# S-Puck-mcu.net
KiCad netlist of a schematic drawn in EAGLE
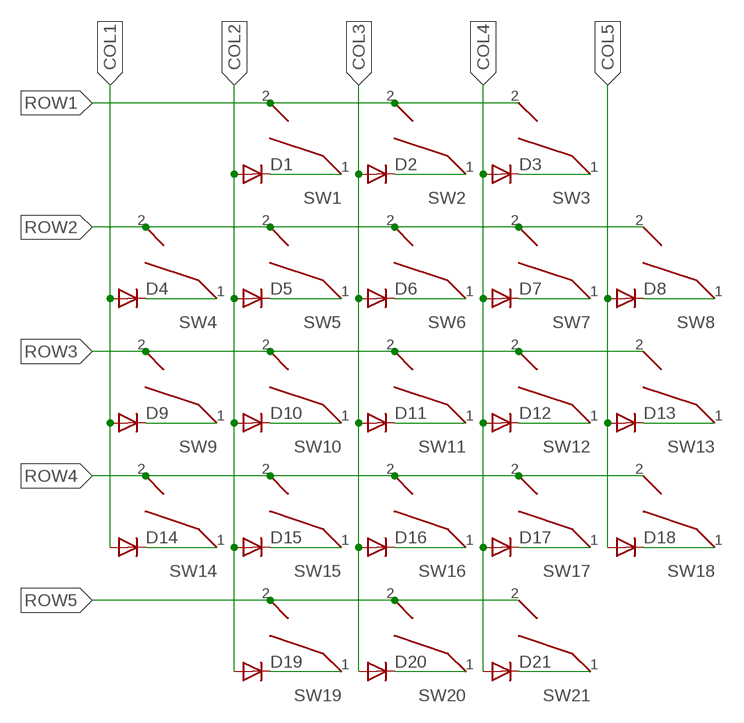
[diagram p0: schematic, sheet 1]
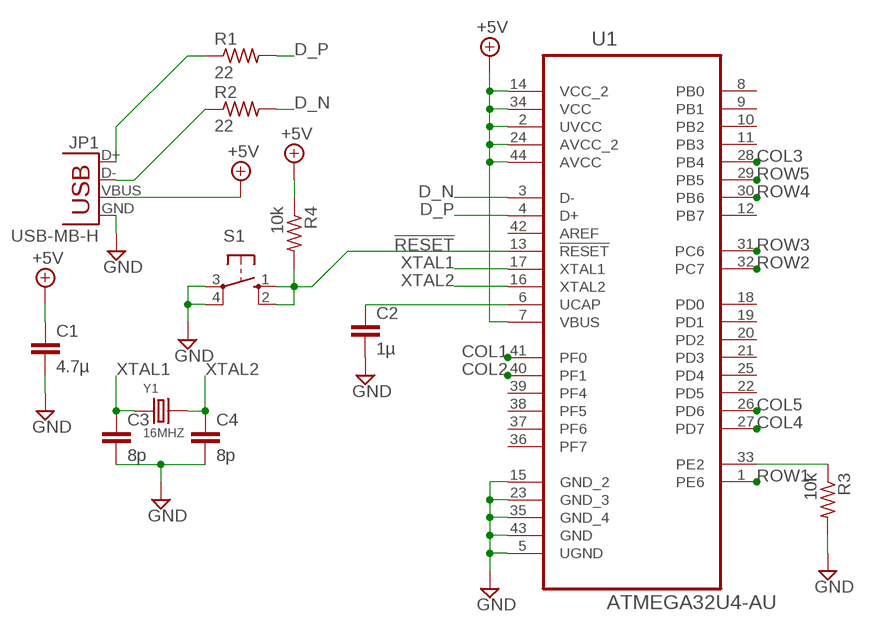
[diagram p1: schematic, sheet 2]

(export (version "E")
  (design (tool "Eeschema 10.0.6"))
  (components
    (comp (ref "D1")
      (value "1N4148DO35-10")
      (footprint "eagle-import:DO35-10")
      (libsource (lib "eagle-import") (part "1N4148DO35-10"))
    )
    (comp (ref "D2")
      (value "1N4148DO35-10")
      (footprint "eagle-import:DO35-10")
      (libsource (lib "eagle-import") (part "1N4148DO35-10"))
    )
    (comp (ref "D3")
      (value "1N4148DO35-10")
      (footprint "eagle-import:DO35-10")
      (libsource (lib "eagle-import") (part "1N4148DO35-10"))
    )
    (comp (ref "D4")
      (value "1N4148DO35-10")
      (footprint "eagle-import:DO35-10")
      (libsource (lib "eagle-import") (part "1N4148DO35-10"))
    )
    (comp (ref "D5")
      (value "1N4148DO35-10")
      (footprint "eagle-import:DO35-10")
      (libsource (lib "eagle-import") (part "1N4148DO35-10"))
    )
    (comp (ref "D6")
      (value "1N4148DO35-10")
      (footprint "eagle-import:DO35-10")
      (libsource (lib "eagle-import") (part "1N4148DO35-10"))
    )
    (comp (ref "D7")
      (value "1N4148DO35-10")
      (footprint "eagle-import:DO35-10")
      (libsource (lib "eagle-import") (part "1N4148DO35-10"))
    )
    (comp (ref "D8")
      (value "1N4148DO35-10")
      (footprint "eagle-import:DO35-10")
      (libsource (lib "eagle-import") (part "1N4148DO35-10"))
    )
    (comp (ref "D9")
      (value "1N4148DO35-10")
      (footprint "eagle-import:DO35-10")
      (libsource (lib "eagle-import") (part "1N4148DO35-10"))
    )
    (comp (ref "D10")
      (value "1N4148DO35-10")
      (footprint "eagle-import:DO35-10")
      (libsource (lib "eagle-import") (part "1N4148DO35-10"))
    )
    (comp (ref "D11")
      (value "1N4148DO35-10")
      (footprint "eagle-import:DO35-10")
      (libsource (lib "eagle-import") (part "1N4148DO35-10"))
    )
    (comp (ref "D12")
      (value "1N4148DO35-10")
      (footprint "eagle-import:DO35-10")
      (libsource (lib "eagle-import") (part "1N4148DO35-10"))
    )
    (comp (ref "D13")
      (value "1N4148DO35-10")
      (footprint "eagle-import:DO35-10")
      (libsource (lib "eagle-import") (part "1N4148DO35-10"))
    )
    (comp (ref "D14")
      (value "1N4148DO35-10")
      (footprint "eagle-import:DO35-10")
      (libsource (lib "eagle-import") (part "1N4148DO35-10"))
    )
    (comp (ref "D15")
      (value "1N4148DO35-10")
      (footprint "eagle-import:DO35-10")
      (libsource (lib "eagle-import") (part "1N4148DO35-10"))
    )
    (comp (ref "D16")
      (value "1N4148DO35-10")
      (footprint "eagle-import:DO35-10")
      (libsource (lib "eagle-import") (part "1N4148DO35-10"))
    )
    (comp (ref "D17")
      (value "1N4148DO35-10")
      (footprint "eagle-import:DO35-10")
      (libsource (lib "eagle-import") (part "1N4148DO35-10"))
    )
    (comp (ref "D18")
      (value "1N4148DO35-10")
      (footprint "eagle-import:DO35-10")
      (libsource (lib "eagle-import") (part "1N4148DO35-10"))
    )
    (comp (ref "D19")
      (value "1N4148DO35-10")
      (footprint "eagle-import:DO35-10")
      (libsource (lib "eagle-import") (part "1N4148DO35-10"))
    )
    (comp (ref "D20")
      (value "1N4148DO35-10")
      (footprint "eagle-import:DO35-10")
      (libsource (lib "eagle-import") (part "1N4148DO35-10"))
    )
    (comp (ref "D21")
      (value "1N4148DO35-10")
      (footprint "eagle-import:DO35-10")
      (libsource (lib "eagle-import") (part "1N4148DO35-10"))
    )
    (comp (ref "SW1")
      (value "CHERRY_MX_WITH_FIXING_PINS")
      (footprint "eagle-import:MX1A-XXNW")
      (libsource (lib "eagle-import") (part "CHERRY_MX_WITH_FIXING_PINS"))
    )
    (comp (ref "SW2")
      (value "CHERRY_MX_WITH_FIXING_PINS")
      (footprint "eagle-import:MX1A-XXNW")
      (libsource (lib "eagle-import") (part "CHERRY_MX_WITH_FIXING_PINS"))
    )
    (comp (ref "SW3")
      (value "CHERRY_MX_WITH_FIXING_PINS")
      (footprint "eagle-import:MX1A-XXNW")
      (libsource (lib "eagle-import") (part "CHERRY_MX_WITH_FIXING_PINS"))
    )
    (comp (ref "SW4")
      (value "CHERRY_MX_WITH_FIXING_PINS")
      (footprint "eagle-import:MX1A-XXNW")
      (libsource (lib "eagle-import") (part "CHERRY_MX_WITH_FIXING_PINS"))
    )
    (comp (ref "SW5")
      (value "CHERRY_MX_WITH_FIXING_PINS")
      (footprint "eagle-import:MX1A-XXNW")
      (libsource (lib "eagle-import") (part "CHERRY_MX_WITH_FIXING_PINS"))
    )
    (comp (ref "SW6")
      (value "CHERRY_MX_WITH_FIXING_PINS")
      (footprint "eagle-import:MX1A-XXNW")
      (libsource (lib "eagle-import") (part "CHERRY_MX_WITH_FIXING_PINS"))
    )
    (comp (ref "SW7")
      (value "CHERRY_MX_WITH_FIXING_PINS")
      (footprint "eagle-import:MX1A-XXNW")
      (libsource (lib "eagle-import") (part "CHERRY_MX_WITH_FIXING_PINS"))
    )
    (comp (ref "SW8")
      (value "CHERRY_MX_WITH_FIXING_PINS")
      (footprint "eagle-import:MX1A-XXNW")
      (libsource (lib "eagle-import") (part "CHERRY_MX_WITH_FIXING_PINS"))
    )
    (comp (ref "SW9")
      (value "CHERRY_MX_WITH_FIXING_PINS")
      (footprint "eagle-import:MX1A-XXNW")
      (libsource (lib "eagle-import") (part "CHERRY_MX_WITH_FIXING_PINS"))
    )
    (comp (ref "SW10")
      (value "CHERRY_MX_WITH_FIXING_PINS")
      (footprint "eagle-import:MX1A-XXNW")
      (libsource (lib "eagle-import") (part "CHERRY_MX_WITH_FIXING_PINS"))
    )
    (comp (ref "SW11")
      (value "CHERRY_MX_WITH_FIXING_PINS")
      (footprint "eagle-import:MX1A-XXNW")
      (libsource (lib "eagle-import") (part "CHERRY_MX_WITH_FIXING_PINS"))
    )
    (comp (ref "SW12")
      (value "CHERRY_MX_WITH_FIXING_PINS")
      (footprint "eagle-import:MX1A-XXNW")
      (libsource (lib "eagle-import") (part "CHERRY_MX_WITH_FIXING_PINS"))
    )
    (comp (ref "SW13")
      (value "CHERRY_MX_WITH_FIXING_PINS")
      (footprint "eagle-import:MX1A-XXNW")
      (libsource (lib "eagle-import") (part "CHERRY_MX_WITH_FIXING_PINS"))
    )
    (comp (ref "SW14")
      (value "CHERRY_MX_WITH_FIXING_PINS")
      (footprint "eagle-import:MX1A-XXNW")
      (libsource (lib "eagle-import") (part "CHERRY_MX_WITH_FIXING_PINS"))
    )
    (comp (ref "SW15")
      (value "CHERRY_MX_WITH_FIXING_PINS")
      (footprint "eagle-import:MX1A-XXNW")
      (libsource (lib "eagle-import") (part "CHERRY_MX_WITH_FIXING_PINS"))
    )
    (comp (ref "SW16")
      (value "CHERRY_MX_WITH_FIXING_PINS")
      (footprint "eagle-import:MX1A-XXNW")
      (libsource (lib "eagle-import") (part "CHERRY_MX_WITH_FIXING_PINS"))
    )
    (comp (ref "SW17")
      (value "CHERRY_MX_WITH_FIXING_PINS")
      (footprint "eagle-import:MX1A-XXNW")
      (libsource (lib "eagle-import") (part "CHERRY_MX_WITH_FIXING_PINS"))
    )
    (comp (ref "SW18")
      (value "CHERRY_MX_WITH_FIXING_PINS")
      (footprint "eagle-import:MX1A-XXNW")
      (libsource (lib "eagle-import") (part "CHERRY_MX_WITH_FIXING_PINS"))
    )
    (comp (ref "SW19")
      (value "CHERRY_MX_WITH_FIXING_PINS")
      (footprint "eagle-import:MX1A-XXNW")
      (libsource (lib "eagle-import") (part "CHERRY_MX_WITH_FIXING_PINS"))
    )
    (comp (ref "SW20")
      (value "CHERRY_MX_WITH_FIXING_PINS")
      (footprint "eagle-import:MX1A-XXNW")
      (libsource (lib "eagle-import") (part "CHERRY_MX_WITH_FIXING_PINS"))
    )
    (comp (ref "SW21")
      (value "CHERRY_MX_WITH_FIXING_PINS")
      (footprint "eagle-import:MX1A-XXNW")
      (libsource (lib "eagle-import") (part "CHERRY_MX_WITH_FIXING_PINS"))
    )
    (comp (ref "C1")
      (value "4.7µ")
      (footprint "eagle-import:C0805K")
      (libsource (lib "eagle-import") (part "C-EUC0805K"))
    )
    (comp (ref "C2")
      (value "1µ")
      (footprint "eagle-import:C0805K")
      (libsource (lib "eagle-import") (part "C-EUC0805K"))
    )
    (comp (ref "C3")
      (value "8p")
      (footprint "eagle-import:C0805K")
      (libsource (lib "eagle-import") (part "C-EUC0805K"))
    )
    (comp (ref "C4")
      (value "8p")
      (footprint "eagle-import:C0805K")
      (libsource (lib "eagle-import") (part "C-EUC0805K"))
    )
    (comp (ref "JP1")
      (value "USB-MB-H")
      (footprint "eagle-import:USB-MB-H")
      (libsource (lib "eagle-import") (part "USB-MB-H"))
    )
    (comp (ref "R1")
      (value "22")
      (footprint "eagle-import:R0805W")
      (libsource (lib "eagle-import") (part "R-US_R0805W"))
    )
    (comp (ref "R2")
      (value "22")
      (footprint "eagle-import:R0805W")
      (libsource (lib "eagle-import") (part "R-US_R0805W"))
    )
    (comp (ref "R3")
      (value "10k")
      (footprint "eagle-import:R0805W")
      (libsource (lib "eagle-import") (part "R-US_R0805W"))
    )
    (comp (ref "R4")
      (value "10k")
      (footprint "eagle-import:R0805W")
      (libsource (lib "eagle-import") (part "R-US_R0805W"))
    )
    (comp (ref "S1")
      (value "10-XX")
      (footprint "eagle-import:B3F-10XX")
      (fields (field (name "MPN") "B3F-1000"))
      (libsource (lib "eagle-import") (part "10-XX"))
    )
    (comp (ref "U1")
      (value "ATMEGA32U4-AU")
      (footprint "eagle-import:QFP80P1200X1200X120-44N")
      (libsource (lib "eagle-import") (part "ATMEGA32U4-AU"))
    )
    (comp (ref "Y1")
      (value "16MHZ")
      (footprint "eagle-import:X2-SMD-5.0X3.2X1.3MM")
      (fields (field (name "MPN") "X053201602002"))
      (libsource (lib "eagle-import") (part "SMD-CRYSTAL-16MHZ-8PF-20PPM-40R(2P-5.0X3.2MM)"))
    )
  )
  (nets
    (net (code "1") (name "+5V") (class "Default")
      (node (ref "C1") (pin "1") (pinfunction "1_1") (pintype "passive"))
      (node (ref "JP1") (pin "VBUS") (pinfunction "VBUS_VBUS") (pintype "bidirectional"))
      (node (ref "R4") (pin "1") (pinfunction "1_1") (pintype "passive"))
      (node (ref "U1") (pin "14") (pinfunction "VCC_2_14") (pintype "power_in"))
      (node (ref "U1") (pin "2") (pinfunction "UVCC_2") (pintype "power_in"))
      (node (ref "U1") (pin "24") (pinfunction "AVCC_2_24") (pintype "power_in"))
      (node (ref "U1") (pin "34") (pinfunction "VCC_34") (pintype "power_in"))
      (node (ref "U1") (pin "44") (pinfunction "AVCC_44") (pintype "power_in"))
      (node (ref "U1") (pin "7") (pinfunction "VBUS_7") (pintype "input"))
    )
    (net (code "2") (name "COL1") (class "Default")
      (node (ref "D14") (pin "A") (pinfunction "A_A") (pintype "passive"))
      (node (ref "D4") (pin "A") (pinfunction "A_A") (pintype "passive"))
      (node (ref "D9") (pin "A") (pinfunction "A_A") (pintype "passive"))
      (node (ref "U1") (pin "41") (pinfunction "PF0_41") (pintype "bidirectional"))
    )
    (net (code "3") (name "COL2") (class "Default")
      (node (ref "D1") (pin "A") (pinfunction "A_A") (pintype "passive"))
      (node (ref "D10") (pin "A") (pinfunction "A_A") (pintype "passive"))
      (node (ref "D15") (pin "A") (pinfunction "A_A") (pintype "passive"))
      (node (ref "D19") (pin "A") (pinfunction "A_A") (pintype "passive"))
      (node (ref "D5") (pin "A") (pinfunction "A_A") (pintype "passive"))
      (node (ref "U1") (pin "40") (pinfunction "PF1_40") (pintype "bidirectional"))
    )
    (net (code "4") (name "COL3") (class "Default")
      (node (ref "D11") (pin "A") (pinfunction "A_A") (pintype "passive"))
      (node (ref "D16") (pin "A") (pinfunction "A_A") (pintype "passive"))
      (node (ref "D2") (pin "A") (pinfunction "A_A") (pintype "passive"))
      (node (ref "D20") (pin "A") (pinfunction "A_A") (pintype "passive"))
      (node (ref "D6") (pin "A") (pinfunction "A_A") (pintype "passive"))
      (node (ref "U1") (pin "28") (pinfunction "PB4_28") (pintype "bidirectional"))
    )
    (net (code "5") (name "COL4") (class "Default")
      (node (ref "D12") (pin "A") (pinfunction "A_A") (pintype "passive"))
      (node (ref "D17") (pin "A") (pinfunction "A_A") (pintype "passive"))
      (node (ref "D21") (pin "A") (pinfunction "A_A") (pintype "passive"))
      (node (ref "D3") (pin "A") (pinfunction "A_A") (pintype "passive"))
      (node (ref "D7") (pin "A") (pinfunction "A_A") (pintype "passive"))
      (node (ref "U1") (pin "27") (pinfunction "PD7_27") (pintype "bidirectional"))
    )
    (net (code "6") (name "COL5") (class "Default")
      (node (ref "D13") (pin "A") (pinfunction "A_A") (pintype "passive"))
      (node (ref "D18") (pin "A") (pinfunction "A_A") (pintype "passive"))
      (node (ref "D8") (pin "A") (pinfunction "A_A") (pintype "passive"))
      (node (ref "U1") (pin "26") (pinfunction "PD6_26") (pintype "bidirectional"))
    )
    (net (code "7") (name "D_N") (class "Default")
      (node (ref "R2") (pin "2") (pinfunction "2_2") (pintype "passive"))
      (node (ref "U1") (pin "3") (pinfunction "D-_3") (pintype "passive"))
    )
    (net (code "8") (name "D_P") (class "Default")
      (node (ref "R1") (pin "2") (pinfunction "2_2") (pintype "passive"))
      (node (ref "U1") (pin "4") (pinfunction "D+_4") (pintype "passive"))
    )
    (net (code "9") (name "GND") (class "Default")
      (node (ref "C1") (pin "2") (pinfunction "2_2") (pintype "passive"))
      (node (ref "C2") (pin "2") (pinfunction "2_2") (pintype "passive"))
      (node (ref "C3") (pin "2") (pinfunction "2_2") (pintype "passive"))
      (node (ref "C4") (pin "2") (pinfunction "2_2") (pintype "passive"))
      (node (ref "JP1") (pin "GND") (pinfunction "GND_GND") (pintype "bidirectional"))
      (node (ref "R3") (pin "2") (pinfunction "2_2") (pintype "passive"))
      (node (ref "S1") (pin "3") (pinfunction "P_3") (pintype "passive"))
      (node (ref "S1") (pin "4") (pinfunction "P1_4") (pintype "passive"))
      (node (ref "U1") (pin "15") (pinfunction "GND_2_15") (pintype "passive"))
      (node (ref "U1") (pin "23") (pinfunction "GND_3_23") (pintype "passive"))
      (node (ref "U1") (pin "35") (pinfunction "GND_4_35") (pintype "passive"))
      (node (ref "U1") (pin "43") (pinfunction "GND_43") (pintype "passive"))
      (node (ref "U1") (pin "5") (pinfunction "UGND_5") (pintype "passive"))
    )
    (net (code "10") (name "Net-(D1-PadC)") (class "Default")
      (node (ref "D1") (pin "C") (pinfunction "C_C") (pintype "passive"))
      (node (ref "SW1") (pin "1") (pinfunction "1_1") (pintype "passive"))
    )
    (net (code "11") (name "Net-(D2-PadC)") (class "Default")
      (node (ref "D2") (pin "C") (pinfunction "C_C") (pintype "passive"))
      (node (ref "SW2") (pin "1") (pinfunction "1_1") (pintype "passive"))
    )
    (net (code "12") (name "Net-(D3-PadC)") (class "Default")
      (node (ref "D3") (pin "C") (pinfunction "C_C") (pintype "passive"))
      (node (ref "SW3") (pin "1") (pinfunction "1_1") (pintype "passive"))
    )
    (net (code "13") (name "Net-(D4-PadC)") (class "Default")
      (node (ref "D4") (pin "C") (pinfunction "C_C") (pintype "passive"))
      (node (ref "SW4") (pin "1") (pinfunction "1_1") (pintype "passive"))
    )
    (net (code "14") (name "Net-(D5-PadC)") (class "Default")
      (node (ref "D5") (pin "C") (pinfunction "C_C") (pintype "passive"))
      (node (ref "SW5") (pin "1") (pinfunction "1_1") (pintype "passive"))
    )
    (net (code "15") (name "Net-(D6-PadC)") (class "Default")
      (node (ref "D6") (pin "C") (pinfunction "C_C") (pintype "passive"))
      (node (ref "SW6") (pin "1") (pinfunction "1_1") (pintype "passive"))
    )
    (net (code "16") (name "Net-(D7-PadC)") (class "Default")
      (node (ref "D7") (pin "C") (pinfunction "C_C") (pintype "passive"))
      (node (ref "SW7") (pin "1") (pinfunction "1_1") (pintype "passive"))
    )
    (net (code "17") (name "Net-(D8-PadC)") (class "Default")
      (node (ref "D8") (pin "C") (pinfunction "C_C") (pintype "passive"))
      (node (ref "SW8") (pin "1") (pinfunction "1_1") (pintype "passive"))
    )
    (net (code "18") (name "Net-(D9-PadC)") (class "Default")
      (node (ref "D9") (pin "C") (pinfunction "C_C") (pintype "passive"))
      (node (ref "SW9") (pin "1") (pinfunction "1_1") (pintype "passive"))
    )
    (net (code "19") (name "Net-(D10-PadC)") (class "Default")
      (node (ref "D10") (pin "C") (pinfunction "C_C") (pintype "passive"))
      (node (ref "SW10") (pin "1") (pinfunction "1_1") (pintype "passive"))
    )
    (net (code "20") (name "Net-(D11-PadC)") (class "Default")
      (node (ref "D11") (pin "C") (pinfunction "C_C") (pintype "passive"))
      (node (ref "SW11") (pin "1") (pinfunction "1_1") (pintype "passive"))
    )
    (net (code "21") (name "Net-(D12-PadC)") (class "Default")
      (node (ref "D12") (pin "C") (pinfunction "C_C") (pintype "passive"))
      (node (ref "SW12") (pin "1") (pinfunction "1_1") (pintype "passive"))
    )
    (net (code "22") (name "Net-(D13-PadC)") (class "Default")
      (node (ref "D13") (pin "C") (pinfunction "C_C") (pintype "passive"))
      (node (ref "SW13") (pin "1") (pinfunction "1_1") (pintype "passive"))
    )
    (net (code "23") (name "Net-(D14-PadC)") (class "Default")
      (node (ref "D14") (pin "C") (pinfunction "C_C") (pintype "passive"))
      (node (ref "SW14") (pin "1") (pinfunction "1_1") (pintype "passive"))
    )
    (net (code "24") (name "Net-(D15-PadC)") (class "Default")
      (node (ref "D15") (pin "C") (pinfunction "C_C") (pintype "passive"))
      (node (ref "SW15") (pin "1") (pinfunction "1_1") (pintype "passive"))
    )
    (net (code "25") (name "Net-(D16-PadC)") (class "Default")
      (node (ref "D16") (pin "C") (pinfunction "C_C") (pintype "passive"))
      (node (ref "SW16") (pin "1") (pinfunction "1_1") (pintype "passive"))
    )
    (net (code "26") (name "Net-(D17-PadC)") (class "Default")
      (node (ref "D17") (pin "C") (pinfunction "C_C") (pintype "passive"))
      (node (ref "SW17") (pin "1") (pinfunction "1_1") (pintype "passive"))
    )
    (net (code "27") (name "Net-(D18-PadC)") (class "Default")
      (node (ref "D18") (pin "C") (pinfunction "C_C") (pintype "passive"))
      (node (ref "SW18") (pin "1") (pinfunction "1_1") (pintype "passive"))
    )
    (net (code "28") (name "Net-(D19-PadC)") (class "Default")
      (node (ref "D19") (pin "C") (pinfunction "C_C") (pintype "passive"))
      (node (ref "SW19") (pin "1") (pinfunction "1_1") (pintype "passive"))
    )
    (net (code "29") (name "Net-(D20-PadC)") (class "Default")
      (node (ref "D20") (pin "C") (pinfunction "C_C") (pintype "passive"))
      (node (ref "SW20") (pin "1") (pinfunction "1_1") (pintype "passive"))
    )
    (net (code "30") (name "Net-(D21-PadC)") (class "Default")
      (node (ref "D21") (pin "C") (pinfunction "C_C") (pintype "passive"))
      (node (ref "SW21") (pin "1") (pinfunction "1_1") (pintype "passive"))
    )
    (net (code "31") (name "Net-(JP1-PadD+)") (class "Default")
      (node (ref "JP1") (pin "D+") (pinfunction "D+_D+") (pintype "bidirectional"))
      (node (ref "R1") (pin "1") (pinfunction "1_1") (pintype "passive"))
    )
    (net (code "32") (name "Net-(JP1-PadD-)") (class "Default")
      (node (ref "JP1") (pin "D-") (pinfunction "D-_D-") (pintype "bidirectional"))
      (node (ref "R2") (pin "1") (pinfunction "1_1") (pintype "passive"))
    )
    (net (code "33") (name "Net-(U1-PE2)") (class "Default")
      (node (ref "R3") (pin "1") (pinfunction "1_1") (pintype "passive"))
      (node (ref "U1") (pin "33") (pinfunction "PE2_33") (pintype "bidirectional"))
    )
    (net (code "34") (name "Net-(U1-UCAP)") (class "Default")
      (node (ref "C2") (pin "1") (pinfunction "1_1") (pintype "passive"))
      (node (ref "U1") (pin "6") (pinfunction "UCAP_6") (pintype "power_in"))
    )
    (net (code "35") (name "ROW1") (class "Default")
      (node (ref "SW1") (pin "2") (pinfunction "2_2") (pintype "passive"))
      (node (ref "SW2") (pin "2") (pinfunction "2_2") (pintype "passive"))
      (node (ref "SW3") (pin "2") (pinfunction "2_2") (pintype "passive"))
      (node (ref "U1") (pin "1") (pinfunction "PE6_1") (pintype "bidirectional"))
    )
    (net (code "36") (name "ROW2") (class "Default")
      (node (ref "SW4") (pin "2") (pinfunction "2_2") (pintype "passive"))
      (node (ref "SW5") (pin "2") (pinfunction "2_2") (pintype "passive"))
      (node (ref "SW6") (pin "2") (pinfunction "2_2") (pintype "passive"))
      (node (ref "SW7") (pin "2") (pinfunction "2_2") (pintype "passive"))
      (node (ref "SW8") (pin "2") (pinfunction "2_2") (pintype "passive"))
      (node (ref "U1") (pin "32") (pinfunction "PC7_32") (pintype "bidirectional"))
    )
    (net (code "37") (name "ROW3") (class "Default")
      (node (ref "SW10") (pin "2") (pinfunction "2_2") (pintype "passive"))
      (node (ref "SW11") (pin "2") (pinfunction "2_2") (pintype "passive"))
      (node (ref "SW12") (pin "2") (pinfunction "2_2") (pintype "passive"))
      (node (ref "SW13") (pin "2") (pinfunction "2_2") (pintype "passive"))
      (node (ref "SW9") (pin "2") (pinfunction "2_2") (pintype "passive"))
      (node (ref "U1") (pin "31") (pinfunction "PC6_31") (pintype "bidirectional"))
    )
    (net (code "38") (name "ROW4") (class "Default")
      (node (ref "SW14") (pin "2") (pinfunction "2_2") (pintype "passive"))
      (node (ref "SW15") (pin "2") (pinfunction "2_2") (pintype "passive"))
      (node (ref "SW16") (pin "2") (pinfunction "2_2") (pintype "passive"))
      (node (ref "SW17") (pin "2") (pinfunction "2_2") (pintype "passive"))
      (node (ref "SW18") (pin "2") (pinfunction "2_2") (pintype "passive"))
      (node (ref "U1") (pin "30") (pinfunction "PB6_30") (pintype "bidirectional"))
    )
    (net (code "39") (name "ROW5") (class "Default")
      (node (ref "SW19") (pin "2") (pinfunction "2_2") (pintype "passive"))
      (node (ref "SW20") (pin "2") (pinfunction "2_2") (pintype "passive"))
      (node (ref "SW21") (pin "2") (pinfunction "2_2") (pintype "passive"))
      (node (ref "U1") (pin "29") (pinfunction "PB5_29") (pintype "bidirectional"))
    )
    (net (code "40") (name "XTAL1") (class "Default")
      (node (ref "C3") (pin "1") (pinfunction "1_1") (pintype "passive"))
      (node (ref "U1") (pin "17") (pinfunction "XTAL1_17") (pintype "input"))
      (node (ref "Y1") (pin "1") (pinfunction "1_1") (pintype "passive"))
    )
    (net (code "41") (name "XTAL2") (class "Default")
      (node (ref "C4") (pin "1") (pinfunction "1_1") (pintype "passive"))
      (node (ref "U1") (pin "16") (pinfunction "XTAL2_16") (pintype "output"))
      (node (ref "Y1") (pin "2") (pinfunction "2_2") (pintype "passive"))
    )
    (net (code "42") (name "unconnected-(U1-AREF-Pad42)") (class "Default")
      (node (ref "U1") (pin "42") (pinfunction "AREF_42") (pintype "input"))
    )
    (net (code "43") (name "unconnected-(U1-PB0-Pad8)") (class "Default")
      (node (ref "U1") (pin "8") (pinfunction "PB0_8") (pintype "bidirectional"))
    )
    (net (code "44") (name "unconnected-(U1-PB1-Pad9)") (class "Default")
      (node (ref "U1") (pin "9") (pinfunction "PB1_9") (pintype "bidirectional"))
    )
    (net (code "45") (name "unconnected-(U1-PB2-Pad10)") (class "Default")
      (node (ref "U1") (pin "10") (pinfunction "PB2_10") (pintype "bidirectional"))
    )
    (net (code "46") (name "unconnected-(U1-PB3-Pad11)") (class "Default")
      (node (ref "U1") (pin "11") (pinfunction "PB3_11") (pintype "bidirectional"))
    )
    (net (code "47") (name "unconnected-(U1-PB7-Pad12)") (class "Default")
      (node (ref "U1") (pin "12") (pinfunction "PB7_12") (pintype "bidirectional"))
    )
    (net (code "48") (name "unconnected-(U1-PD0-Pad18)") (class "Default")
      (node (ref "U1") (pin "18") (pinfunction "PD0_18") (pintype "bidirectional"))
    )
    (net (code "49") (name "unconnected-(U1-PD1-Pad19)") (class "Default")
      (node (ref "U1") (pin "19") (pinfunction "PD1_19") (pintype "bidirectional"))
    )
    (net (code "50") (name "unconnected-(U1-PD2-Pad20)") (class "Default")
      (node (ref "U1") (pin "20") (pinfunction "PD2_20") (pintype "bidirectional"))
    )
    (net (code "51") (name "unconnected-(U1-PD3-Pad21)") (class "Default")
      (node (ref "U1") (pin "21") (pinfunction "PD3_21") (pintype "bidirectional"))
    )
    (net (code "52") (name "unconnected-(U1-PD4-Pad25)") (class "Default")
      (node (ref "U1") (pin "25") (pinfunction "PD4_25") (pintype "bidirectional"))
    )
    (net (code "53") (name "unconnected-(U1-PD5-Pad22)") (class "Default")
      (node (ref "U1") (pin "22") (pinfunction "PD5_22") (pintype "bidirectional"))
    )
    (net (code "54") (name "unconnected-(U1-PF4-Pad39)") (class "Default")
      (node (ref "U1") (pin "39") (pinfunction "PF4_39") (pintype "bidirectional"))
    )
    (net (code "55") (name "unconnected-(U1-PF5-Pad38)") (class "Default")
      (node (ref "U1") (pin "38") (pinfunction "PF5_38") (pintype "bidirectional"))
    )
    (net (code "56") (name "unconnected-(U1-PF6-Pad37)") (class "Default")
      (node (ref "U1") (pin "37") (pinfunction "PF6_37") (pintype "bidirectional"))
    )
    (net (code "57") (name "unconnected-(U1-PF7-Pad36)") (class "Default")
      (node (ref "U1") (pin "36") (pinfunction "PF7_36") (pintype "bidirectional"))
    )
    (net (code "58") (name "~{RESET}") (class "Default")
      (node (ref "R4") (pin "2") (pinfunction "2_2") (pintype "passive"))
      (node (ref "S1") (pin "1") (pinfunction "S_1") (pintype "passive"))
      (node (ref "S1") (pin "2") (pinfunction "S1_2") (pintype "passive"))
      (node (ref "U1") (pin "13") (pinfunction "~{RESET}_13") (pintype "input"))
    )
  )
)
